# ServoCity.net
KiCad netlist of a schematic drawn in EAGLE
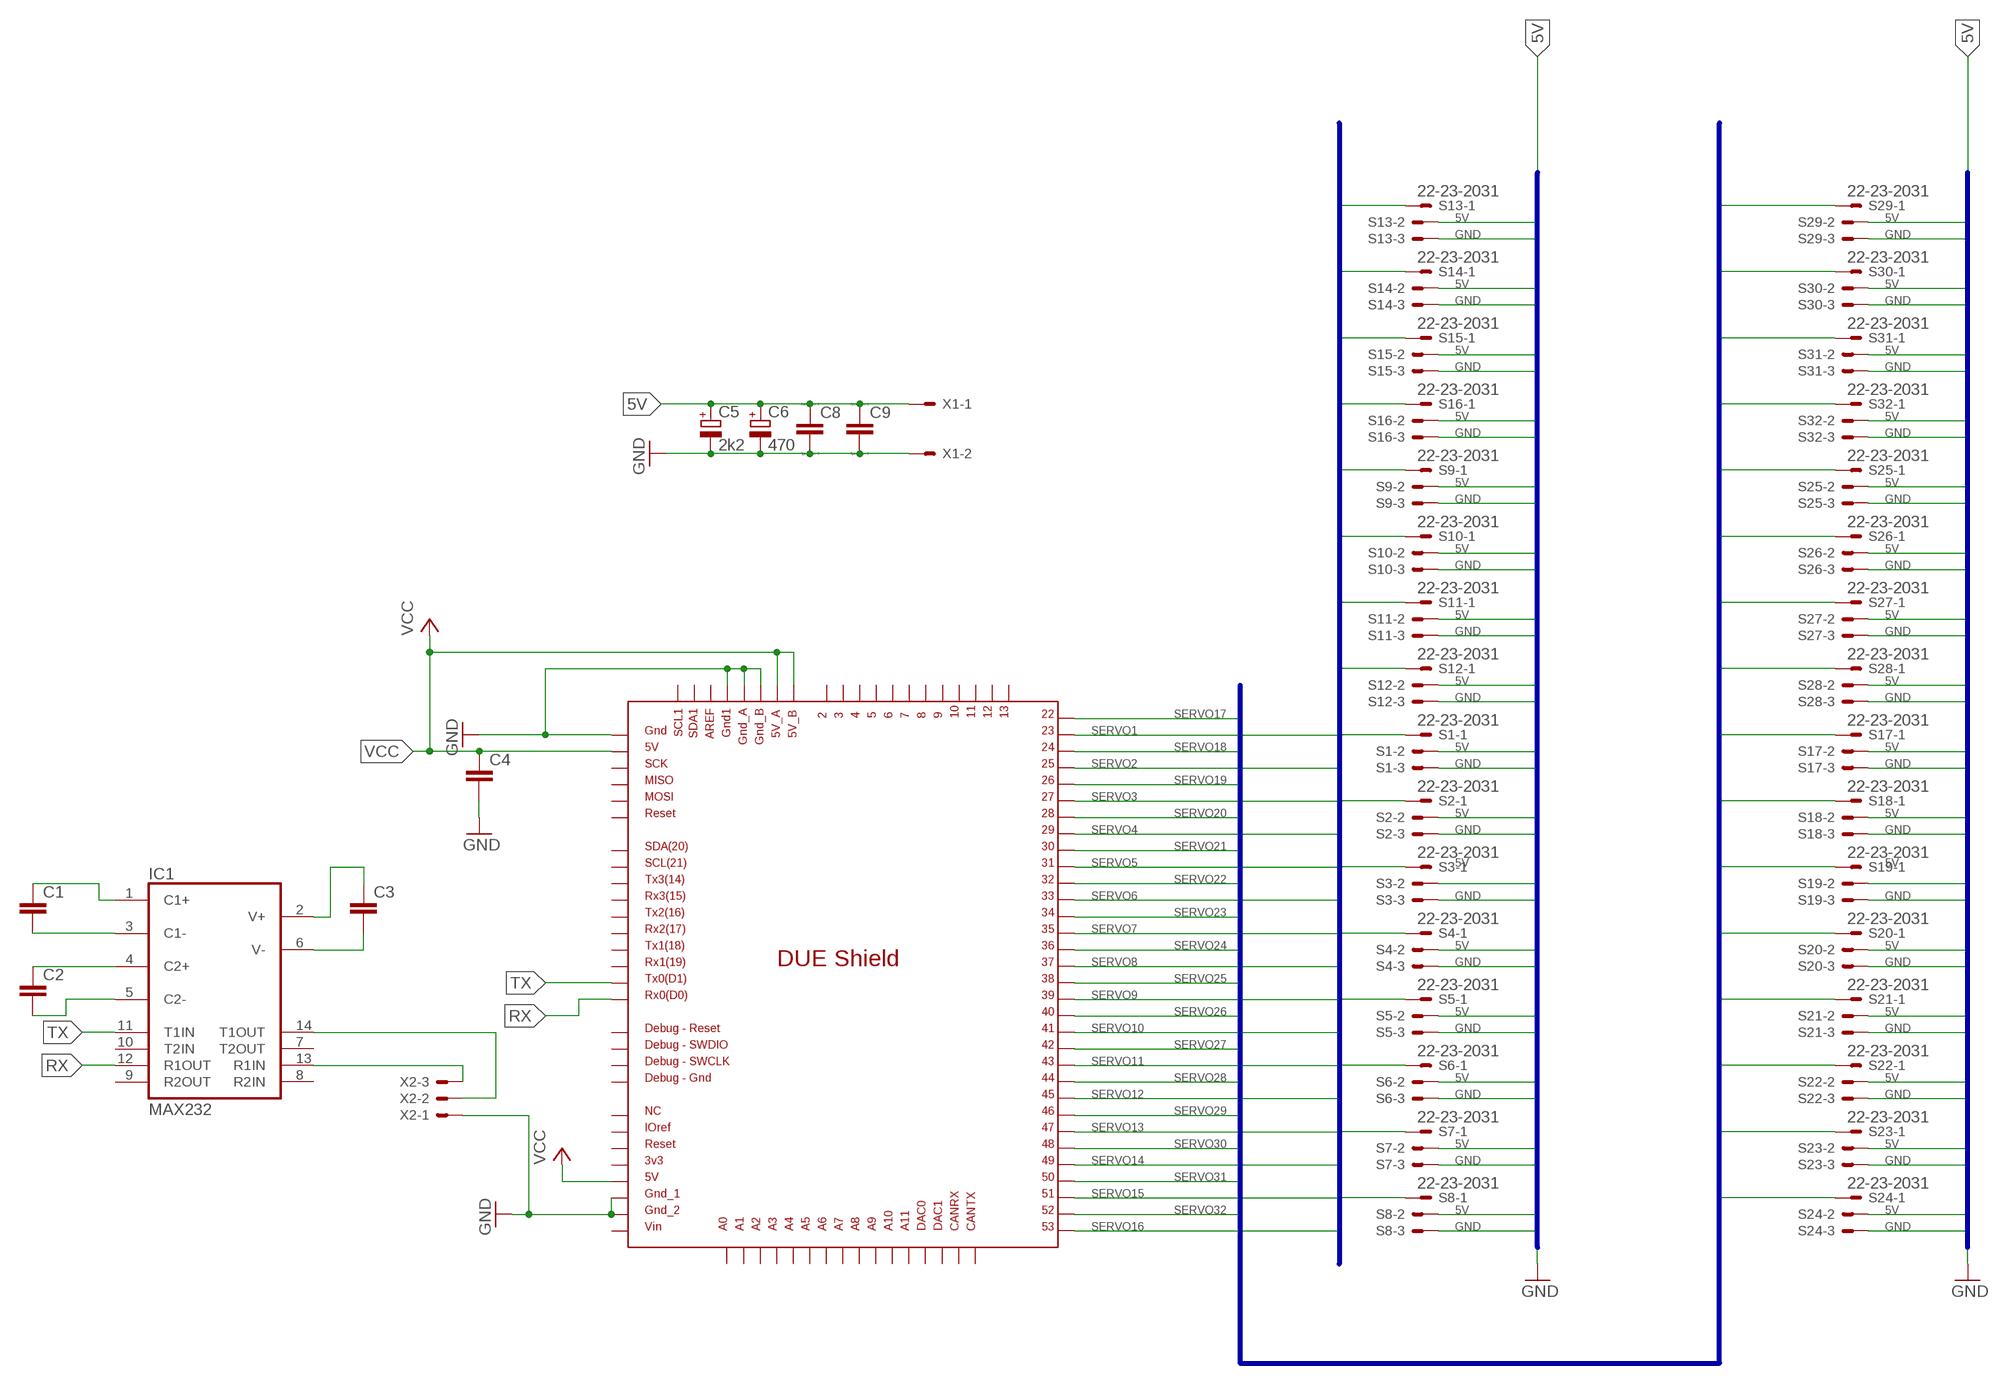
[diagram p0: schematic, sheet 1]

(export (version "E")
  (design (tool "Eeschema 10.0.6"))
  (components
    (comp (ref "C1")
      (value "C-EUC0805")
      (footprint "eagle-import:C0805")
      (libsource (lib "eagle-import") (part "C-EUC0805"))
    )
    (comp (ref "C2")
      (value "C-EUC0805")
      (footprint "eagle-import:C0805")
      (libsource (lib "eagle-import") (part "C-EUC0805"))
    )
    (comp (ref "C3")
      (value "C-EUC0805")
      (footprint "eagle-import:C0805")
      (libsource (lib "eagle-import") (part "C-EUC0805"))
    )
    (comp (ref "C4")
      (value "C-EUC0805")
      (footprint "eagle-import:C0805")
      (libsource (lib "eagle-import") (part "C-EUC0805"))
    )
    (comp (ref "C5")
      (value "2k2")
      (footprint "eagle-import:EB20D")
      (libsource (lib "eagle-import") (part "CPOL-EUE10-20"))
    )
    (comp (ref "C6")
      (value "470")
      (footprint "eagle-import:E5-10,5")
      (libsource (lib "eagle-import") (part "CPOL-EUE5-10.5"))
    )
    (comp (ref "C8") (value "C") (footprint "eagle-import:C0805") (libsource (lib "eagle-import") (part "C")))
    (comp (ref "C9") (value "C") (footprint "eagle-import:C0805") (libsource (lib "eagle-import") (part "C")))
    (comp (ref "IC1")
      (value "MAX232")
      (footprint "eagle-import:DIL16")
      (fields (field (name "MF") "MAXIM") (field (name "MPN") "MAX232ACPE+"))
      (libsource (lib "eagle-import") (part "MAX232"))
    )
    (comp (ref "S1")
      (value "22-23-2031")
      (footprint "eagle-import:22-23-2031")
      (fields (field (name "MF") "MOLEX"))
      (libsource (lib "eagle-import") (part "22-23-2031"))
    )
    (comp (ref "S2")
      (value "22-23-2031")
      (footprint "eagle-import:22-23-2031")
      (fields (field (name "MF") "MOLEX"))
      (libsource (lib "eagle-import") (part "22-23-2031"))
    )
    (comp (ref "S3")
      (value "22-23-2031")
      (footprint "eagle-import:22-23-2031")
      (fields (field (name "MF") "MOLEX"))
      (libsource (lib "eagle-import") (part "22-23-2031"))
    )
    (comp (ref "S4")
      (value "22-23-2031")
      (footprint "eagle-import:22-23-2031")
      (fields (field (name "MF") "MOLEX"))
      (libsource (lib "eagle-import") (part "22-23-2031"))
    )
    (comp (ref "S5")
      (value "22-23-2031")
      (footprint "eagle-import:22-23-2031")
      (fields (field (name "MF") "MOLEX"))
      (libsource (lib "eagle-import") (part "22-23-2031"))
    )
    (comp (ref "S6")
      (value "22-23-2031")
      (footprint "eagle-import:22-23-2031")
      (fields (field (name "MF") "MOLEX"))
      (libsource (lib "eagle-import") (part "22-23-2031"))
    )
    (comp (ref "S7")
      (value "22-23-2031")
      (footprint "eagle-import:22-23-2031")
      (fields (field (name "MF") "MOLEX"))
      (libsource (lib "eagle-import") (part "22-23-2031"))
    )
    (comp (ref "S8")
      (value "22-23-2031")
      (footprint "eagle-import:22-23-2031")
      (fields (field (name "MF") "MOLEX"))
      (libsource (lib "eagle-import") (part "22-23-2031"))
    )
    (comp (ref "S9")
      (value "22-23-2031")
      (footprint "eagle-import:22-23-2031")
      (fields (field (name "MF") "MOLEX"))
      (libsource (lib "eagle-import") (part "22-23-2031"))
    )
    (comp (ref "S10")
      (value "22-23-2031")
      (footprint "eagle-import:22-23-2031")
      (fields (field (name "MF") "MOLEX"))
      (libsource (lib "eagle-import") (part "22-23-2031"))
    )
    (comp (ref "S11")
      (value "22-23-2031")
      (footprint "eagle-import:22-23-2031")
      (fields (field (name "MF") "MOLEX"))
      (libsource (lib "eagle-import") (part "22-23-2031"))
    )
    (comp (ref "S12")
      (value "22-23-2031")
      (footprint "eagle-import:22-23-2031")
      (fields (field (name "MF") "MOLEX"))
      (libsource (lib "eagle-import") (part "22-23-2031"))
    )
    (comp (ref "S13")
      (value "22-23-2031")
      (footprint "eagle-import:22-23-2031")
      (fields (field (name "MF") "MOLEX"))
      (libsource (lib "eagle-import") (part "22-23-2031"))
    )
    (comp (ref "S14")
      (value "22-23-2031")
      (footprint "eagle-import:22-23-2031")
      (fields (field (name "MF") "MOLEX"))
      (libsource (lib "eagle-import") (part "22-23-2031"))
    )
    (comp (ref "S15")
      (value "22-23-2031")
      (footprint "eagle-import:22-23-2031")
      (fields (field (name "MF") "MOLEX"))
      (libsource (lib "eagle-import") (part "22-23-2031"))
    )
    (comp (ref "S16")
      (value "22-23-2031")
      (footprint "eagle-import:22-23-2031")
      (fields (field (name "MF") "MOLEX"))
      (libsource (lib "eagle-import") (part "22-23-2031"))
    )
    (comp (ref "S17")
      (value "22-23-2031")
      (footprint "eagle-import:22-23-2031")
      (fields (field (name "MF") "MOLEX"))
      (libsource (lib "eagle-import") (part "22-23-2031"))
    )
    (comp (ref "S18")
      (value "22-23-2031")
      (footprint "eagle-import:22-23-2031")
      (fields (field (name "MF") "MOLEX"))
      (libsource (lib "eagle-import") (part "22-23-2031"))
    )
    (comp (ref "S19")
      (value "22-23-2031")
      (footprint "eagle-import:22-23-2031")
      (fields (field (name "MF") "MOLEX"))
      (libsource (lib "eagle-import") (part "22-23-2031"))
    )
    (comp (ref "S20")
      (value "22-23-2031")
      (footprint "eagle-import:22-23-2031")
      (fields (field (name "MF") "MOLEX"))
      (libsource (lib "eagle-import") (part "22-23-2031"))
    )
    (comp (ref "S21")
      (value "22-23-2031")
      (footprint "eagle-import:22-23-2031")
      (fields (field (name "MF") "MOLEX"))
      (libsource (lib "eagle-import") (part "22-23-2031"))
    )
    (comp (ref "S22")
      (value "22-23-2031")
      (footprint "eagle-import:22-23-2031")
      (fields (field (name "MF") "MOLEX"))
      (libsource (lib "eagle-import") (part "22-23-2031"))
    )
    (comp (ref "S23")
      (value "22-23-2031")
      (footprint "eagle-import:22-23-2031")
      (fields (field (name "MF") "MOLEX"))
      (libsource (lib "eagle-import") (part "22-23-2031"))
    )
    (comp (ref "S24")
      (value "22-23-2031")
      (footprint "eagle-import:22-23-2031")
      (fields (field (name "MF") "MOLEX"))
      (libsource (lib "eagle-import") (part "22-23-2031"))
    )
    (comp (ref "S25")
      (value "22-23-2031")
      (footprint "eagle-import:22-23-2031")
      (fields (field (name "MF") "MOLEX"))
      (libsource (lib "eagle-import") (part "22-23-2031"))
    )
    (comp (ref "S26")
      (value "22-23-2031")
      (footprint "eagle-import:22-23-2031")
      (fields (field (name "MF") "MOLEX"))
      (libsource (lib "eagle-import") (part "22-23-2031"))
    )
    (comp (ref "S27")
      (value "22-23-2031")
      (footprint "eagle-import:22-23-2031")
      (fields (field (name "MF") "MOLEX"))
      (libsource (lib "eagle-import") (part "22-23-2031"))
    )
    (comp (ref "S28")
      (value "22-23-2031")
      (footprint "eagle-import:22-23-2031")
      (fields (field (name "MF") "MOLEX"))
      (libsource (lib "eagle-import") (part "22-23-2031"))
    )
    (comp (ref "S29")
      (value "22-23-2031")
      (footprint "eagle-import:22-23-2031")
      (fields (field (name "MF") "MOLEX"))
      (libsource (lib "eagle-import") (part "22-23-2031"))
    )
    (comp (ref "S30")
      (value "22-23-2031")
      (footprint "eagle-import:22-23-2031")
      (fields (field (name "MF") "MOLEX"))
      (libsource (lib "eagle-import") (part "22-23-2031"))
    )
    (comp (ref "S31")
      (value "22-23-2031")
      (footprint "eagle-import:22-23-2031")
      (fields (field (name "MF") "MOLEX"))
      (libsource (lib "eagle-import") (part "22-23-2031"))
    )
    (comp (ref "S32")
      (value "22-23-2031")
      (footprint "eagle-import:22-23-2031")
      (fields (field (name "MF") "MOLEX"))
      (libsource (lib "eagle-import") (part "22-23-2031"))
    )
    (comp (ref "U$1")
      (value "DUE(NORMAL)")
      (footprint "eagle-import:DUE(NORMAL)")
      (libsource (lib "eagle-import") (part "DUE(NORMAL)"))
    )
    (comp (ref "X1")
      (value "KK-156-2")
      (footprint "eagle-import:KK-156-2")
      (libsource (lib "eagle-import") (part "KK-156-2"))
    )
    (comp (ref "X2")
      (value "KK-156-3")
      (footprint "eagle-import:KK-156-3")
      (libsource (lib "eagle-import") (part "KK-156-3"))
    )
  )
  (nets
    (net (code "1") (name "/SERVO1") (class "Default")
      (node (ref "S1") (pin "1") (pinfunction "S_1") (pintype "passive"))
      (node (ref "U$1") (pin "23") (pinfunction "23_23") (pintype "bidirectional"))
    )
    (net (code "2") (name "/SERVO2") (class "Default")
      (node (ref "S2") (pin "1") (pinfunction "S_1") (pintype "passive"))
      (node (ref "U$1") (pin "25") (pinfunction "25_25") (pintype "bidirectional"))
    )
    (net (code "3") (name "/SERVO3") (class "Default")
      (node (ref "S3") (pin "1") (pinfunction "S_1") (pintype "passive"))
      (node (ref "U$1") (pin "27") (pinfunction "27_27") (pintype "bidirectional"))
    )
    (net (code "4") (name "/SERVO4") (class "Default")
      (node (ref "S4") (pin "1") (pinfunction "S_1") (pintype "passive"))
      (node (ref "U$1") (pin "29") (pinfunction "29_29") (pintype "bidirectional"))
    )
    (net (code "5") (name "/SERVO5") (class "Default")
      (node (ref "S5") (pin "1") (pinfunction "S_1") (pintype "passive"))
      (node (ref "U$1") (pin "31") (pinfunction "31_31") (pintype "bidirectional"))
    )
    (net (code "6") (name "/SERVO6") (class "Default")
      (node (ref "S6") (pin "1") (pinfunction "S_1") (pintype "passive"))
      (node (ref "U$1") (pin "33") (pinfunction "33_33") (pintype "bidirectional"))
    )
    (net (code "7") (name "/SERVO7") (class "Default")
      (node (ref "S7") (pin "1") (pinfunction "S_1") (pintype "passive"))
      (node (ref "U$1") (pin "35") (pinfunction "35_35") (pintype "bidirectional"))
    )
    (net (code "8") (name "/SERVO8") (class "Default")
      (node (ref "S8") (pin "1") (pinfunction "S_1") (pintype "passive"))
      (node (ref "U$1") (pin "37") (pinfunction "37_37") (pintype "bidirectional"))
    )
    (net (code "9") (name "/SERVO9") (class "Default")
      (node (ref "S9") (pin "1") (pinfunction "S_1") (pintype "passive"))
      (node (ref "U$1") (pin "39") (pinfunction "39_39") (pintype "bidirectional"))
    )
    (net (code "10") (name "/SERVO10") (class "Default")
      (node (ref "S10") (pin "1") (pinfunction "S_1") (pintype "passive"))
      (node (ref "U$1") (pin "41") (pinfunction "41_41") (pintype "bidirectional"))
    )
    (net (code "11") (name "/SERVO11") (class "Default")
      (node (ref "S11") (pin "1") (pinfunction "S_1") (pintype "passive"))
      (node (ref "U$1") (pin "43") (pinfunction "43_43") (pintype "bidirectional"))
    )
    (net (code "12") (name "/SERVO12") (class "Default")
      (node (ref "S12") (pin "1") (pinfunction "S_1") (pintype "passive"))
      (node (ref "U$1") (pin "45") (pinfunction "45_45") (pintype "bidirectional"))
    )
    (net (code "13") (name "/SERVO13") (class "Default")
      (node (ref "S13") (pin "1") (pinfunction "S_1") (pintype "passive"))
      (node (ref "U$1") (pin "47") (pinfunction "47_47") (pintype "bidirectional"))
    )
    (net (code "14") (name "/SERVO14") (class "Default")
      (node (ref "S14") (pin "1") (pinfunction "S_1") (pintype "passive"))
      (node (ref "U$1") (pin "49") (pinfunction "49_49") (pintype "bidirectional"))
    )
    (net (code "15") (name "/SERVO15") (class "Default")
      (node (ref "S15") (pin "1") (pinfunction "S_1") (pintype "passive"))
      (node (ref "U$1") (pin "51") (pinfunction "51_51") (pintype "bidirectional"))
    )
    (net (code "16") (name "/SERVO16") (class "Default")
      (node (ref "S16") (pin "1") (pinfunction "S_1") (pintype "passive"))
      (node (ref "U$1") (pin "53") (pinfunction "53_53") (pintype "bidirectional"))
    )
    (net (code "17") (name "/SERVO17") (class "Default")
      (node (ref "S17") (pin "1") (pinfunction "S_1") (pintype "passive"))
      (node (ref "U$1") (pin "22") (pinfunction "22_22") (pintype "bidirectional"))
    )
    (net (code "18") (name "/SERVO18") (class "Default")
      (node (ref "S18") (pin "1") (pinfunction "S_1") (pintype "passive"))
      (node (ref "U$1") (pin "24") (pinfunction "24_24") (pintype "bidirectional"))
    )
    (net (code "19") (name "/SERVO19") (class "Default")
      (node (ref "S19") (pin "1") (pinfunction "S_1") (pintype "passive"))
      (node (ref "U$1") (pin "26") (pinfunction "26_26") (pintype "bidirectional"))
    )
    (net (code "20") (name "/SERVO20") (class "Default")
      (node (ref "S20") (pin "1") (pinfunction "S_1") (pintype "passive"))
      (node (ref "U$1") (pin "28") (pinfunction "28_28") (pintype "bidirectional"))
    )
    (net (code "21") (name "/SERVO21") (class "Default")
      (node (ref "S21") (pin "1") (pinfunction "S_1") (pintype "passive"))
      (node (ref "U$1") (pin "30") (pinfunction "30_30") (pintype "bidirectional"))
    )
    (net (code "22") (name "/SERVO22") (class "Default")
      (node (ref "S22") (pin "1") (pinfunction "S_1") (pintype "passive"))
      (node (ref "U$1") (pin "32") (pinfunction "32_32") (pintype "bidirectional"))
    )
    (net (code "23") (name "/SERVO23") (class "Default")
      (node (ref "S23") (pin "1") (pinfunction "S_1") (pintype "passive"))
      (node (ref "U$1") (pin "34") (pinfunction "34_34") (pintype "bidirectional"))
    )
    (net (code "24") (name "/SERVO24") (class "Default")
      (node (ref "S24") (pin "1") (pinfunction "S_1") (pintype "passive"))
      (node (ref "U$1") (pin "36") (pinfunction "36_36") (pintype "bidirectional"))
    )
    (net (code "25") (name "/SERVO25") (class "Default")
      (node (ref "S25") (pin "1") (pinfunction "S_1") (pintype "passive"))
      (node (ref "U$1") (pin "38") (pinfunction "38_38") (pintype "bidirectional"))
    )
    (net (code "26") (name "/SERVO26") (class "Default")
      (node (ref "S26") (pin "1") (pinfunction "S_1") (pintype "passive"))
      (node (ref "U$1") (pin "40") (pinfunction "40_40") (pintype "bidirectional"))
    )
    (net (code "27") (name "/SERVO27") (class "Default")
      (node (ref "S27") (pin "1") (pinfunction "S_1") (pintype "passive"))
      (node (ref "U$1") (pin "42") (pinfunction "42_42") (pintype "bidirectional"))
    )
    (net (code "28") (name "/SERVO28") (class "Default")
      (node (ref "S28") (pin "1") (pinfunction "S_1") (pintype "passive"))
      (node (ref "U$1") (pin "44") (pinfunction "44_44") (pintype "bidirectional"))
    )
    (net (code "29") (name "/SERVO29") (class "Default")
      (node (ref "S29") (pin "1") (pinfunction "S_1") (pintype "passive"))
      (node (ref "U$1") (pin "46") (pinfunction "46_46") (pintype "bidirectional"))
    )
    (net (code "30") (name "/SERVO30") (class "Default")
      (node (ref "S30") (pin "1") (pinfunction "S_1") (pintype "passive"))
      (node (ref "U$1") (pin "48") (pinfunction "48_48") (pintype "bidirectional"))
    )
    (net (code "31") (name "/SERVO31") (class "Default")
      (node (ref "S31") (pin "1") (pinfunction "S_1") (pintype "passive"))
      (node (ref "U$1") (pin "50") (pinfunction "50_50") (pintype "bidirectional"))
    )
    (net (code "32") (name "/SERVO32") (class "Default")
      (node (ref "S32") (pin "1") (pinfunction "S_1") (pintype "passive"))
      (node (ref "U$1") (pin "52") (pinfunction "52_52") (pintype "bidirectional"))
    )
    (net (code "33") (name "5V") (class "Default")
      (node (ref "C5") (pin "+") (pinfunction "+_+") (pintype "passive"))
      (node (ref "C6") (pin "+") (pinfunction "+_+") (pintype "passive"))
      (node (ref "C8") (pin "1") (pinfunction "1_1") (pintype "passive"))
      (node (ref "C9") (pin "1") (pinfunction "1_1") (pintype "passive"))
      (node (ref "S1") (pin "2") (pinfunction "S_2") (pintype "passive"))
      (node (ref "S10") (pin "2") (pinfunction "S_2") (pintype "passive"))
      (node (ref "S11") (pin "2") (pinfunction "S_2") (pintype "passive"))
      (node (ref "S12") (pin "2") (pinfunction "S_2") (pintype "passive"))
      (node (ref "S13") (pin "2") (pinfunction "S_2") (pintype "passive"))
      (node (ref "S14") (pin "2") (pinfunction "S_2") (pintype "passive"))
      (node (ref "S15") (pin "2") (pinfunction "S_2") (pintype "passive"))
      (node (ref "S16") (pin "2") (pinfunction "S_2") (pintype "passive"))
      (node (ref "S17") (pin "2") (pinfunction "S_2") (pintype "passive"))
      (node (ref "S18") (pin "2") (pinfunction "S_2") (pintype "passive"))
      (node (ref "S19") (pin "2") (pinfunction "S_2") (pintype "passive"))
      (node (ref "S2") (pin "2") (pinfunction "S_2") (pintype "passive"))
      (node (ref "S20") (pin "2") (pinfunction "S_2") (pintype "passive"))
      (node (ref "S21") (pin "2") (pinfunction "S_2") (pintype "passive"))
      (node (ref "S22") (pin "2") (pinfunction "S_2") (pintype "passive"))
      (node (ref "S23") (pin "2") (pinfunction "S_2") (pintype "passive"))
      (node (ref "S24") (pin "2") (pinfunction "S_2") (pintype "passive"))
      (node (ref "S25") (pin "2") (pinfunction "S_2") (pintype "passive"))
      (node (ref "S26") (pin "2") (pinfunction "S_2") (pintype "passive"))
      (node (ref "S27") (pin "2") (pinfunction "S_2") (pintype "passive"))
      (node (ref "S28") (pin "2") (pinfunction "S_2") (pintype "passive"))
      (node (ref "S29") (pin "2") (pinfunction "S_2") (pintype "passive"))
      (node (ref "S3") (pin "2") (pinfunction "S_2") (pintype "passive"))
      (node (ref "S30") (pin "2") (pinfunction "S_2") (pintype "passive"))
      (node (ref "S31") (pin "2") (pinfunction "S_2") (pintype "passive"))
      (node (ref "S32") (pin "2") (pinfunction "S_2") (pintype "passive"))
      (node (ref "S4") (pin "2") (pinfunction "S_2") (pintype "passive"))
      (node (ref "S5") (pin "2") (pinfunction "S_2") (pintype "passive"))
      (node (ref "S6") (pin "2") (pinfunction "S_2") (pintype "passive"))
      (node (ref "S7") (pin "2") (pinfunction "S_2") (pintype "passive"))
      (node (ref "S8") (pin "2") (pinfunction "S_2") (pintype "passive"))
      (node (ref "S9") (pin "2") (pinfunction "S_2") (pintype "passive"))
      (node (ref "X1") (pin "1") (pinfunction "S_1") (pintype "passive"))
    )
    (net (code "34") (name "GND") (class "Default")
      (node (ref "C4") (pin "2") (pinfunction "2_2") (pintype "passive"))
      (node (ref "C5") (pin "-") (pinfunction "-_-") (pintype "passive"))
      (node (ref "C6") (pin "-") (pinfunction "-_-") (pintype "passive"))
      (node (ref "C8") (pin "2") (pinfunction "2_2") (pintype "passive"))
      (node (ref "C9") (pin "2") (pinfunction "2_2") (pintype "passive"))
      (node (ref "S1") (pin "3") (pinfunction "S_3") (pintype "passive"))
      (node (ref "S10") (pin "3") (pinfunction "S_3") (pintype "passive"))
      (node (ref "S11") (pin "3") (pinfunction "S_3") (pintype "passive"))
      (node (ref "S12") (pin "3") (pinfunction "S_3") (pintype "passive"))
      (node (ref "S13") (pin "3") (pinfunction "S_3") (pintype "passive"))
      (node (ref "S14") (pin "3") (pinfunction "S_3") (pintype "passive"))
      (node (ref "S15") (pin "3") (pinfunction "S_3") (pintype "passive"))
      (node (ref "S16") (pin "3") (pinfunction "S_3") (pintype "passive"))
      (node (ref "S17") (pin "3") (pinfunction "S_3") (pintype "passive"))
      (node (ref "S18") (pin "3") (pinfunction "S_3") (pintype "passive"))
      (node (ref "S19") (pin "3") (pinfunction "S_3") (pintype "passive"))
      (node (ref "S2") (pin "3") (pinfunction "S_3") (pintype "passive"))
      (node (ref "S20") (pin "3") (pinfunction "S_3") (pintype "passive"))
      (node (ref "S21") (pin "3") (pinfunction "S_3") (pintype "passive"))
      (node (ref "S22") (pin "3") (pinfunction "S_3") (pintype "passive"))
      (node (ref "S23") (pin "3") (pinfunction "S_3") (pintype "passive"))
      (node (ref "S24") (pin "3") (pinfunction "S_3") (pintype "passive"))
      (node (ref "S25") (pin "3") (pinfunction "S_3") (pintype "passive"))
      (node (ref "S26") (pin "3") (pinfunction "S_3") (pintype "passive"))
      (node (ref "S27") (pin "3") (pinfunction "S_3") (pintype "passive"))
      (node (ref "S28") (pin "3") (pinfunction "S_3") (pintype "passive"))
      (node (ref "S29") (pin "3") (pinfunction "S_3") (pintype "passive"))
      (node (ref "S3") (pin "3") (pinfunction "S_3") (pintype "passive"))
      (node (ref "S30") (pin "3") (pinfunction "S_3") (pintype "passive"))
      (node (ref "S31") (pin "3") (pinfunction "S_3") (pintype "passive"))
      (node (ref "S32") (pin "3") (pinfunction "S_3") (pintype "passive"))
      (node (ref "S4") (pin "3") (pinfunction "S_3") (pintype "passive"))
      (node (ref "S5") (pin "3") (pinfunction "S_3") (pintype "passive"))
      (node (ref "S6") (pin "3") (pinfunction "S_3") (pintype "passive"))
      (node (ref "S7") (pin "3") (pinfunction "S_3") (pintype "passive"))
      (node (ref "S8") (pin "3") (pinfunction "S_3") (pintype "passive"))
      (node (ref "S9") (pin "3") (pinfunction "S_3") (pintype "passive"))
      (node (ref "U$1") (pin "5V_ICSP") (pinfunction "5V_ICSP_5V_ICSP") (pintype "bidirectional"))
      (node (ref "U$1") (pin "GND1") (pinfunction "GND1_GND1") (pintype "bidirectional"))
      (node (ref "U$1") (pin "GND_1") (pinfunction "GND_1_GND_1") (pintype "bidirectional"))
      (node (ref "U$1") (pin "GND_2") (pinfunction "GND_2_GND_2") (pintype "bidirectional"))
      (node (ref "U$1") (pin "GND_A") (pinfunction "GND_A_GND_A") (pintype "bidirectional"))
      (node (ref "U$1") (pin "GND_B") (pinfunction "GND_B_GND_B") (pintype "bidirectional"))
      (node (ref "X1") (pin "2") (pinfunction "S_2") (pintype "passive"))
      (node (ref "X2") (pin "1") (pinfunction "S_1") (pintype "passive"))
    )
    (net (code "35") (name "Net-(IC1A-C1+)") (class "Default")
      (node (ref "C1") (pin "1") (pinfunction "1_1") (pintype "passive"))
      (node (ref "IC1") (pin "1") (pinfunction "C1+_1") (pintype "bidirectional"))
    )
    (net (code "36") (name "Net-(IC1A-C1-)") (class "Default")
      (node (ref "C1") (pin "2") (pinfunction "2_2") (pintype "passive"))
      (node (ref "IC1") (pin "3") (pinfunction "C1-_3") (pintype "bidirectional"))
    )
    (net (code "37") (name "Net-(IC1A-C2+)") (class "Default")
      (node (ref "C2") (pin "1") (pinfunction "1_1") (pintype "passive"))
      (node (ref "IC1") (pin "4") (pinfunction "C2+_4") (pintype "bidirectional"))
    )
    (net (code "38") (name "Net-(IC1A-C2-)") (class "Default")
      (node (ref "C2") (pin "2") (pinfunction "2_2") (pintype "passive"))
      (node (ref "IC1") (pin "5") (pinfunction "C2-_5") (pintype "bidirectional"))
    )
    (net (code "39") (name "Net-(IC1A-R1IN)") (class "Default")
      (node (ref "IC1") (pin "13") (pinfunction "R1IN_13") (pintype "input"))
      (node (ref "X2") (pin "3") (pinfunction "S_3") (pintype "passive"))
    )
    (net (code "40") (name "Net-(IC1A-T1OUT)") (class "Default")
      (node (ref "IC1") (pin "14") (pinfunction "T1OUT_14") (pintype "output"))
      (node (ref "X2") (pin "2") (pinfunction "S_2") (pintype "passive"))
    )
    (net (code "41") (name "Net-(IC1A-V+)") (class "Default")
      (node (ref "C3") (pin "1") (pinfunction "1_1") (pintype "passive"))
      (node (ref "IC1") (pin "2") (pinfunction "V+_2") (pintype "bidirectional"))
    )
    (net (code "42") (name "Net-(IC1A-V-)") (class "Default")
      (node (ref "C3") (pin "2") (pinfunction "2_2") (pintype "passive"))
      (node (ref "IC1") (pin "6") (pinfunction "V-_6") (pintype "bidirectional"))
    )
    (net (code "43") (name "RX") (class "Default")
      (node (ref "IC1") (pin "12") (pinfunction "R1OUT_12") (pintype "output"))
      (node (ref "U$1") (pin "RX0") (pinfunction "RX0_RX0") (pintype "bidirectional"))
    )
    (net (code "44") (name "TX") (class "Default")
      (node (ref "IC1") (pin "11") (pinfunction "T1IN_11") (pintype "input"))
      (node (ref "U$1") (pin "TX0") (pinfunction "TX0_TX0") (pintype "bidirectional"))
    )
    (net (code "45") (name "VCC") (class "Default")
      (node (ref "C4") (pin "1") (pinfunction "1_1") (pintype "passive"))
      (node (ref "U$1") (pin "5V") (pinfunction "5V_5V") (pintype "bidirectional"))
      (node (ref "U$1") (pin "5V_A") (pinfunction "5V_A_5V_A") (pintype "bidirectional"))
      (node (ref "U$1") (pin "5V_B") (pinfunction "5V_B_5V_B") (pintype "bidirectional"))
      (node (ref "U$1") (pin "GND_ICSP") (pinfunction "GND_ICSP_GND_ICSP") (pintype "bidirectional"))
    )
    (net (code "46") (name "unconnected-(IC1A-R2IN-Pad8)") (class "Default")
      (node (ref "IC1") (pin "8") (pinfunction "R2IN_8") (pintype "input"))
    )
    (net (code "47") (name "unconnected-(IC1A-R2OUT-Pad9)") (class "Default")
      (node (ref "IC1") (pin "9") (pinfunction "R2OUT_9") (pintype "output"))
    )
    (net (code "48") (name "unconnected-(IC1A-T2IN-Pad10)") (class "Default")
      (node (ref "IC1") (pin "10") (pinfunction "T2IN_10") (pintype "input"))
    )
    (net (code "49") (name "unconnected-(IC1A-T2OUT-Pad7)") (class "Default")
      (node (ref "IC1") (pin "7") (pinfunction "T2OUT_7") (pintype "output"))
    )
    (net (code "50") (name "unconnected-(U$1-Pad2)") (class "Default")
      (node (ref "U$1") (pin "2") (pinfunction "2_2") (pintype "bidirectional"))
    )
    (net (code "51") (name "unconnected-(U$1-Pad3)") (class "Default")
      (node (ref "U$1") (pin "3") (pinfunction "3_3") (pintype "bidirectional"))
    )
    (net (code "52") (name "unconnected-(U$1-Pad3V3)") (class "Default")
      (node (ref "U$1") (pin "3V3") (pinfunction "3V3_3V3") (pintype "bidirectional"))
    )
    (net (code "53") (name "unconnected-(U$1-Pad4)") (class "Default")
      (node (ref "U$1") (pin "4") (pinfunction "4_4") (pintype "bidirectional"))
    )
    (net (code "54") (name "unconnected-(U$1-Pad5)") (class "Default")
      (node (ref "U$1") (pin "5") (pinfunction "5_5") (pintype "bidirectional"))
    )
    (net (code "55") (name "unconnected-(U$1-Pad6)") (class "Default")
      (node (ref "U$1") (pin "6") (pinfunction "6_6") (pintype "bidirectional"))
    )
    (net (code "56") (name "unconnected-(U$1-Pad7)") (class "Default")
      (node (ref "U$1") (pin "7") (pinfunction "7_7") (pintype "bidirectional"))
    )
    (net (code "57") (name "unconnected-(U$1-Pad8)") (class "Default")
      (node (ref "U$1") (pin "8") (pinfunction "8_8") (pintype "bidirectional"))
    )
    (net (code "58") (name "unconnected-(U$1-Pad9)") (class "Default")
      (node (ref "U$1") (pin "9") (pinfunction "9_9") (pintype "bidirectional"))
    )
    (net (code "59") (name "unconnected-(U$1-Pad10)") (class "Default")
      (node (ref "U$1") (pin "10") (pinfunction "10_10") (pintype "bidirectional"))
    )
    (net (code "60") (name "unconnected-(U$1-Pad11)") (class "Default")
      (node (ref "U$1") (pin "11") (pinfunction "11_11") (pintype "bidirectional"))
    )
    (net (code "61") (name "unconnected-(U$1-Pad12)") (class "Default")
      (node (ref "U$1") (pin "12") (pinfunction "12_12") (pintype "bidirectional"))
    )
    (net (code "62") (name "unconnected-(U$1-Pad13)") (class "Default")
      (node (ref "U$1") (pin "13") (pinfunction "13_13") (pintype "bidirectional"))
    )
    (net (code "63") (name "unconnected-(U$1-PadA0)") (class "Default")
      (node (ref "U$1") (pin "A0") (pinfunction "A0_A0") (pintype "bidirectional"))
    )
    (net (code "64") (name "unconnected-(U$1-PadA1)") (class "Default")
      (node (ref "U$1") (pin "A1") (pinfunction "A1_A1") (pintype "bidirectional"))
    )
    (net (code "65") (name "unconnected-(U$1-PadA2)") (class "Default")
      (node (ref "U$1") (pin "A2") (pinfunction "A2_A2") (pintype "bidirectional"))
    )
    (net (code "66") (name "unconnected-(U$1-PadA3)") (class "Default")
      (node (ref "U$1") (pin "A3") (pinfunction "A3_A3") (pintype "bidirectional"))
    )
    (net (code "67") (name "unconnected-(U$1-PadA4)") (class "Default")
      (node (ref "U$1") (pin "A4") (pinfunction "A4_A4") (pintype "bidirectional"))
    )
    (net (code "68") (name "unconnected-(U$1-PadA5)") (class "Default")
      (node (ref "U$1") (pin "A5") (pinfunction "A5_A5") (pintype "bidirectional"))
    )
    (net (code "69") (name "unconnected-(U$1-PadA6)") (class "Default")
      (node (ref "U$1") (pin "A6") (pinfunction "A6_A6") (pintype "bidirectional"))
    )
    (net (code "70") (name "unconnected-(U$1-PadA7)") (class "Default")
      (node (ref "U$1") (pin "A7") (pinfunction "A7_A7") (pintype "bidirectional"))
    )
    (net (code "71") (name "unconnected-(U$1-PadA8)") (class "Default")
      (node (ref "U$1") (pin "A8") (pinfunction "A8_A8") (pintype "bidirectional"))
    )
    (net (code "72") (name "unconnected-(U$1-PadA9)") (class "Default")
      (node (ref "U$1") (pin "A9") (pinfunction "A9_A9") (pintype "bidirectional"))
    )
    (net (code "73") (name "unconnected-(U$1-PadA10)") (class "Default")
      (node (ref "U$1") (pin "A10") (pinfunction "A10_A10") (pintype "bidirectional"))
    )
    (net (code "74") (name "unconnected-(U$1-PadA11)") (class "Default")
      (node (ref "U$1") (pin "A11") (pinfunction "A11_A11") (pintype "bidirectional"))
    )
    (net (code "75") (name "unconnected-(U$1-PadAREF)") (class "Default")
      (node (ref "U$1") (pin "AREF") (pinfunction "AREF_AREF") (pintype "bidirectional"))
    )
    (net (code "76") (name "unconnected-(U$1-PadCANRX)") (class "Default")
      (node (ref "U$1") (pin "CANRX") (pinfunction "CANRX_CANRX") (pintype "bidirectional"))
    )
    (net (code "77") (name "unconnected-(U$1-PadCANTX)") (class "Default")
      (node (ref "U$1") (pin "CANTX") (pinfunction "CANTX_CANTX") (pintype "bidirectional"))
    )
    (net (code "78") (name "unconnected-(U$1-PadDAC0)") (class "Default")
      (node (ref "U$1") (pin "DAC0") (pinfunction "DAC0_DAC0") (pintype "bidirectional"))
    )
    (net (code "79") (name "unconnected-(U$1-PadDAC1)") (class "Default")
      (node (ref "U$1") (pin "DAC1") (pinfunction "DAC1_DAC1") (pintype "bidirectional"))
    )
    (net (code "80") (name "unconnected-(U$1-PadGND_DEBUG)") (class "Default")
      (node (ref "U$1") (pin "GND_DEBUG") (pinfunction "GND_DEBUG_GND_DEBUG") (pintype "bidirectional"))
    )
    (net (code "81") (name "unconnected-(U$1-PadIOREF)") (class "Default")
      (node (ref "U$1") (pin "IOREF") (pinfunction "IOREF_IOREF") (pintype "bidirectional"))
    )
    (net (code "82") (name "unconnected-(U$1-PadMISO_ICSP)") (class "Default")
      (node (ref "U$1") (pin "MISO_ICSP") (pinfunction "MISO_ICSP_MISO_ICSP") (pintype "bidirectional"))
    )
    (net (code "83") (name "unconnected-(U$1-PadMOSI_ICSP)") (class "Default")
      (node (ref "U$1") (pin "MOSI_ICSP") (pinfunction "MOSI_ICSP_MOSI_ICSP") (pintype "bidirectional"))
    )
    (net (code "84") (name "unconnected-(U$1-PadNC)") (class "Default")
      (node (ref "U$1") (pin "NC") (pinfunction "NC_NC") (pintype "bidirectional"))
    )
    (net (code "85") (name "unconnected-(U$1-PadRESET)") (class "Default")
      (node (ref "U$1") (pin "RESET") (pinfunction "RESET_RESET") (pintype "bidirectional"))
    )
    (net (code "86") (name "unconnected-(U$1-PadRESET_DEBUG)") (class "Default")
      (node (ref "U$1") (pin "RESET_DEBUG") (pinfunction "RESET_DEBUG_RESET_DEBUG") (pintype "bidirectional"))
    )
    (net (code "87") (name "unconnected-(U$1-PadRESET_ICSP)") (class "Default")
      (node (ref "U$1") (pin "RESET_ICSP") (pinfunction "RESET_ICSP_RESET_ICSP") (pintype "bidirectional"))
    )
    (net (code "88") (name "unconnected-(U$1-PadRX1)") (class "Default")
      (node (ref "U$1") (pin "RX1") (pinfunction "RX1_RX1") (pintype "bidirectional"))
    )
    (net (code "89") (name "unconnected-(U$1-PadRX2)") (class "Default")
      (node (ref "U$1") (pin "RX2") (pinfunction "RX2_RX2") (pintype "bidirectional"))
    )
    (net (code "90") (name "unconnected-(U$1-PadRX3)") (class "Default")
      (node (ref "U$1") (pin "RX3") (pinfunction "RX3_RX3") (pintype "bidirectional"))
    )
    (net (code "91") (name "unconnected-(U$1-PadSCK_ICSP)") (class "Default")
      (node (ref "U$1") (pin "SCK_ICSP") (pinfunction "SCK_ICSP_SCK_ICSP") (pintype "bidirectional"))
    )
    (net (code "92") (name "unconnected-(U$1-PadSCL)") (class "Default")
      (node (ref "U$1") (pin "SCL") (pinfunction "SCL_SCL") (pintype "bidirectional"))
    )
    (net (code "93") (name "unconnected-(U$1-PadSCL1)") (class "Default")
      (node (ref "U$1") (pin "SCL1") (pinfunction "SCL1_SCL1") (pintype "bidirectional"))
    )
    (net (code "94") (name "unconnected-(U$1-PadSDA)") (class "Default")
      (node (ref "U$1") (pin "SDA") (pinfunction "SDA_SDA") (pintype "bidirectional"))
    )
    (net (code "95") (name "unconnected-(U$1-PadSDA1)") (class "Default")
      (node (ref "U$1") (pin "SDA1") (pinfunction "SDA1_SDA1") (pintype "bidirectional"))
    )
    (net (code "96") (name "unconnected-(U$1-PadSWCLK_DEBUG)") (class "Default")
      (node (ref "U$1") (pin "SWCLK_DEBUG") (pinfunction "SWCLK_DEBUG_SWCLK_DEBUG") (pintype "bidirectional"))
    )
    (net (code "97") (name "unconnected-(U$1-PadSWDIO_DEBUG)") (class "Default")
      (node (ref "U$1") (pin "SWDIO_DEBUG") (pinfunction "SWDIO_DEBUG_SWDIO_DEBUG") (pintype "bidirectional"))
    )
    (net (code "98") (name "unconnected-(U$1-PadTX1)") (class "Default")
      (node (ref "U$1") (pin "TX1") (pinfunction "TX1_TX1") (pintype "bidirectional"))
    )
    (net (code "99") (name "unconnected-(U$1-PadTX2)") (class "Default")
      (node (ref "U$1") (pin "TX2") (pinfunction "TX2_TX2") (pintype "bidirectional"))
    )
    (net (code "100") (name "unconnected-(U$1-PadTX3)") (class "Default")
      (node (ref "U$1") (pin "TX3") (pinfunction "TX3_TX3") (pintype "bidirectional"))
    )
    (net (code "101") (name "unconnected-(U$1-PadVIN)") (class "Default")
      (node (ref "U$1") (pin "VIN") (pinfunction "VIN_VIN") (pintype "bidirectional"))
    )
  )
)
